# IoT_Button_with_NeoPixel_BFF.net
KiCad netlist of a schematic drawn in EAGLE
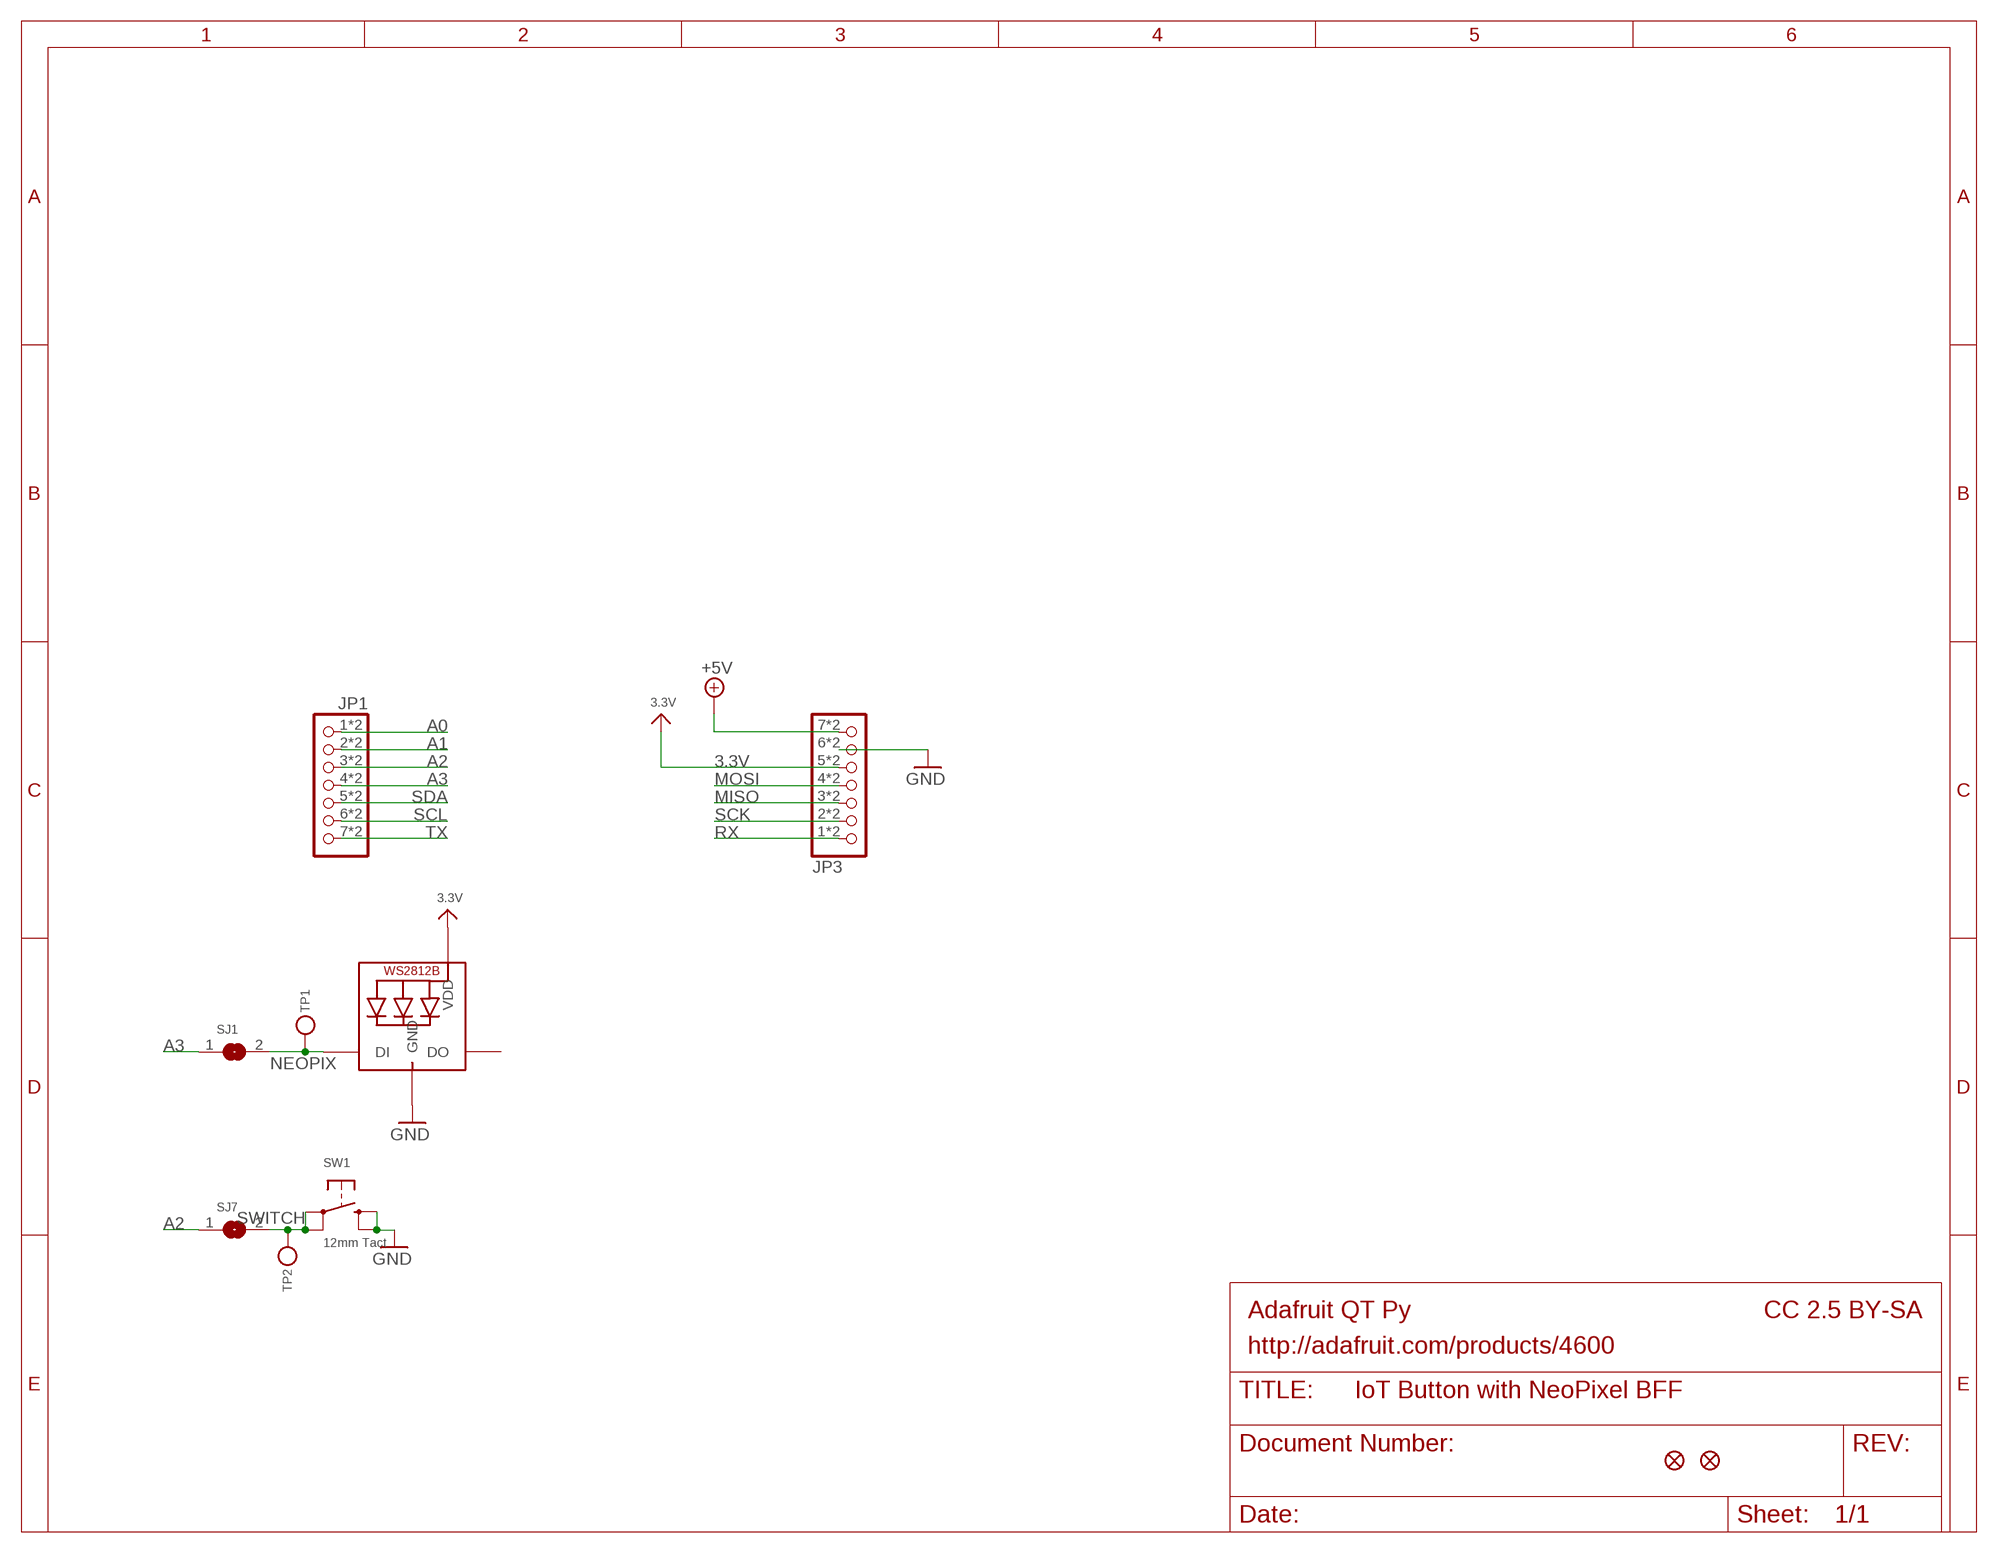
[diagram p0: schematic, sheet 1]

(export (version "E")
  (design (tool "Eeschema 10.0.6"))
  (components
    (comp (ref "JP1")
      (value "HEADER-1X7_CASTEL")
      (footprint "eagle-import:1X07_CASTEL")
      (libsource (lib "eagle-import") (part "HEADER-1X7_CASTEL"))
    )
    (comp (ref "JP3")
      (value "HEADER-1X7_CASTEL")
      (footprint "eagle-import:1X07_CASTEL")
      (libsource (lib "eagle-import") (part "HEADER-1X7_CASTEL"))
    )
    (comp (ref "LED1")
      (value "WS2812B_3535FULL")
      (footprint "eagle-import:LED3535_FULLPADS")
      (libsource (lib "eagle-import") (part "WS2812B_3535FULL"))
    )
    (comp (ref "SJ1")
      (value "SOLDERJUMPERCLOSED")
      (footprint "eagle-import:SOLDERJUMPER_CLOSEDWIRE")
      (libsource (lib "eagle-import") (part "SOLDERJUMPERCLOSED"))
    )
    (comp (ref "SJ7")
      (value "SOLDERJUMPERCLOSED")
      (footprint "eagle-import:SOLDERJUMPER_CLOSEDWIRE")
      (libsource (lib "eagle-import") (part "SOLDERJUMPERCLOSED"))
    )
    (comp (ref "SW1")
      (value "12mm Tact")
      (footprint "eagle-import:B3F-40XX-SMT")
      (libsource (lib "eagle-import") (part "SWITCH_TACT_SMT_12MM"))
    )
    (comp (ref "TP1")
      (value "TESTPOINT1.5X2.0MM_NOCREAM")
      (footprint "eagle-import:PAD-1.5X2.0")
      (libsource (lib "eagle-import") (part "TESTPOINT1.5X2.0MM_NOCREAM"))
    )
    (comp (ref "TP2")
      (value "TESTPOINT1.5X2.0MM_NOCREAM")
      (footprint "eagle-import:PAD-1.5X2.0")
      (libsource (lib "eagle-import") (part "TESTPOINT1.5X2.0MM_NOCREAM"))
    )
    (comp (ref "U$6")
      (value "FIDUCIAL_1MM")
      (footprint "eagle-import:FIDUCIAL_1MM")
      (libsource (lib "eagle-import") (part "FIDUCIAL_1MM"))
    )
    (comp (ref "U$8")
      (value "FIDUCIAL_1MM")
      (footprint "eagle-import:FIDUCIAL_1MM")
      (libsource (lib "eagle-import") (part "FIDUCIAL_1MM"))
    )
  )
  (nets
    (net (code "1") (name "+5V") (class "Default")
      (node (ref "JP3") (pin "7") (pinfunction "7_7") (pintype "passive"))
      (node (ref "JP3") (pin "7C") (pinfunction "7_7C") (pintype "passive"))
    )
    (net (code "2") (name "/A0") (class "Default")
      (node (ref "JP1") (pin "1") (pinfunction "1_1") (pintype "passive"))
      (node (ref "JP1") (pin "1C") (pinfunction "1_1C") (pintype "passive"))
    )
    (net (code "3") (name "/A1") (class "Default")
      (node (ref "JP1") (pin "2") (pinfunction "2_2") (pintype "passive"))
      (node (ref "JP1") (pin "2C") (pinfunction "2_2C") (pintype "passive"))
    )
    (net (code "4") (name "/A2") (class "Default")
      (node (ref "JP1") (pin "3") (pinfunction "3_3") (pintype "passive"))
      (node (ref "JP1") (pin "3C") (pinfunction "3_3C") (pintype "passive"))
      (node (ref "SJ7") (pin "1") (pinfunction "1_1") (pintype "passive"))
    )
    (net (code "5") (name "/A3") (class "Default")
      (node (ref "JP1") (pin "4") (pinfunction "4_4") (pintype "passive"))
      (node (ref "JP1") (pin "4C") (pinfunction "4_4C") (pintype "passive"))
      (node (ref "SJ1") (pin "1") (pinfunction "1_1") (pintype "passive"))
    )
    (net (code "6") (name "/MISO") (class "Default")
      (node (ref "JP3") (pin "3") (pinfunction "3_3") (pintype "passive"))
      (node (ref "JP3") (pin "3C") (pinfunction "3_3C") (pintype "passive"))
    )
    (net (code "7") (name "/MOSI") (class "Default")
      (node (ref "JP3") (pin "4") (pinfunction "4_4") (pintype "passive"))
      (node (ref "JP3") (pin "4C") (pinfunction "4_4C") (pintype "passive"))
    )
    (net (code "8") (name "/NEOPIX") (class "Default")
      (node (ref "LED1") (pin "1") (pinfunction "DI_1") (pintype "input"))
      (node (ref "SJ1") (pin "2") (pinfunction "2_2") (pintype "passive"))
      (node (ref "TP1") (pin "P$1") (pinfunction "P$1_P$1") (pintype "bidirectional"))
    )
    (net (code "9") (name "/RX") (class "Default")
      (node (ref "JP3") (pin "1") (pinfunction "1_1") (pintype "passive"))
      (node (ref "JP3") (pin "1C") (pinfunction "1_1C") (pintype "passive"))
    )
    (net (code "10") (name "/SCK") (class "Default")
      (node (ref "JP3") (pin "2") (pinfunction "2_2") (pintype "passive"))
      (node (ref "JP3") (pin "2C") (pinfunction "2_2C") (pintype "passive"))
    )
    (net (code "11") (name "/SCL") (class "Default")
      (node (ref "JP1") (pin "6") (pinfunction "6_6") (pintype "passive"))
      (node (ref "JP1") (pin "6C") (pinfunction "6_6C") (pintype "passive"))
    )
    (net (code "12") (name "/SDA") (class "Default")
      (node (ref "JP1") (pin "5") (pinfunction "5_5") (pintype "passive"))
      (node (ref "JP1") (pin "5C") (pinfunction "5_5C") (pintype "passive"))
    )
    (net (code "13") (name "/SWITCH") (class "Default")
      (node (ref "SJ7") (pin "2") (pinfunction "2_2") (pintype "passive"))
      (node (ref "SW1") (pin "P$1") (pinfunction "P_P$1") (pintype "passive"))
      (node (ref "SW1") (pin "P$2") (pinfunction "P1_P$2") (pintype "passive"))
      (node (ref "TP2") (pin "P$1") (pinfunction "P$1_P$1") (pintype "bidirectional"))
    )
    (net (code "14") (name "/TX") (class "Default")
      (node (ref "JP1") (pin "7") (pinfunction "7_7") (pintype "passive"))
      (node (ref "JP1") (pin "7C") (pinfunction "7_7C") (pintype "passive"))
    )
    (net (code "15") (name "3.3V") (class "Default")
      (node (ref "JP3") (pin "5") (pinfunction "5_5") (pintype "passive"))
      (node (ref "JP3") (pin "5C") (pinfunction "5_5C") (pintype "passive"))
      (node (ref "LED1") (pin "2") (pinfunction "VDD_2") (pintype "power_in"))
    )
    (net (code "16") (name "GND") (class "Default")
      (node (ref "JP3") (pin "6") (pinfunction "6_6") (pintype "passive"))
      (node (ref "JP3") (pin "6C") (pinfunction "6_6C") (pintype "passive"))
      (node (ref "LED1") (pin "4") (pinfunction "GND_4") (pintype "power_in"))
      (node (ref "SW1") (pin "P$3") (pinfunction "S_P$3") (pintype "passive"))
      (node (ref "SW1") (pin "P$4") (pinfunction "S1_P$4") (pintype "passive"))
    )
    (net (code "17") (name "unconnected-(LED1-DO-Pad3)") (class "Default")
      (node (ref "LED1") (pin "3") (pinfunction "DO_3") (pintype "output"))
    )
  )
)
